# rev1.net
KiCad netlist of a schematic drawn in EAGLE
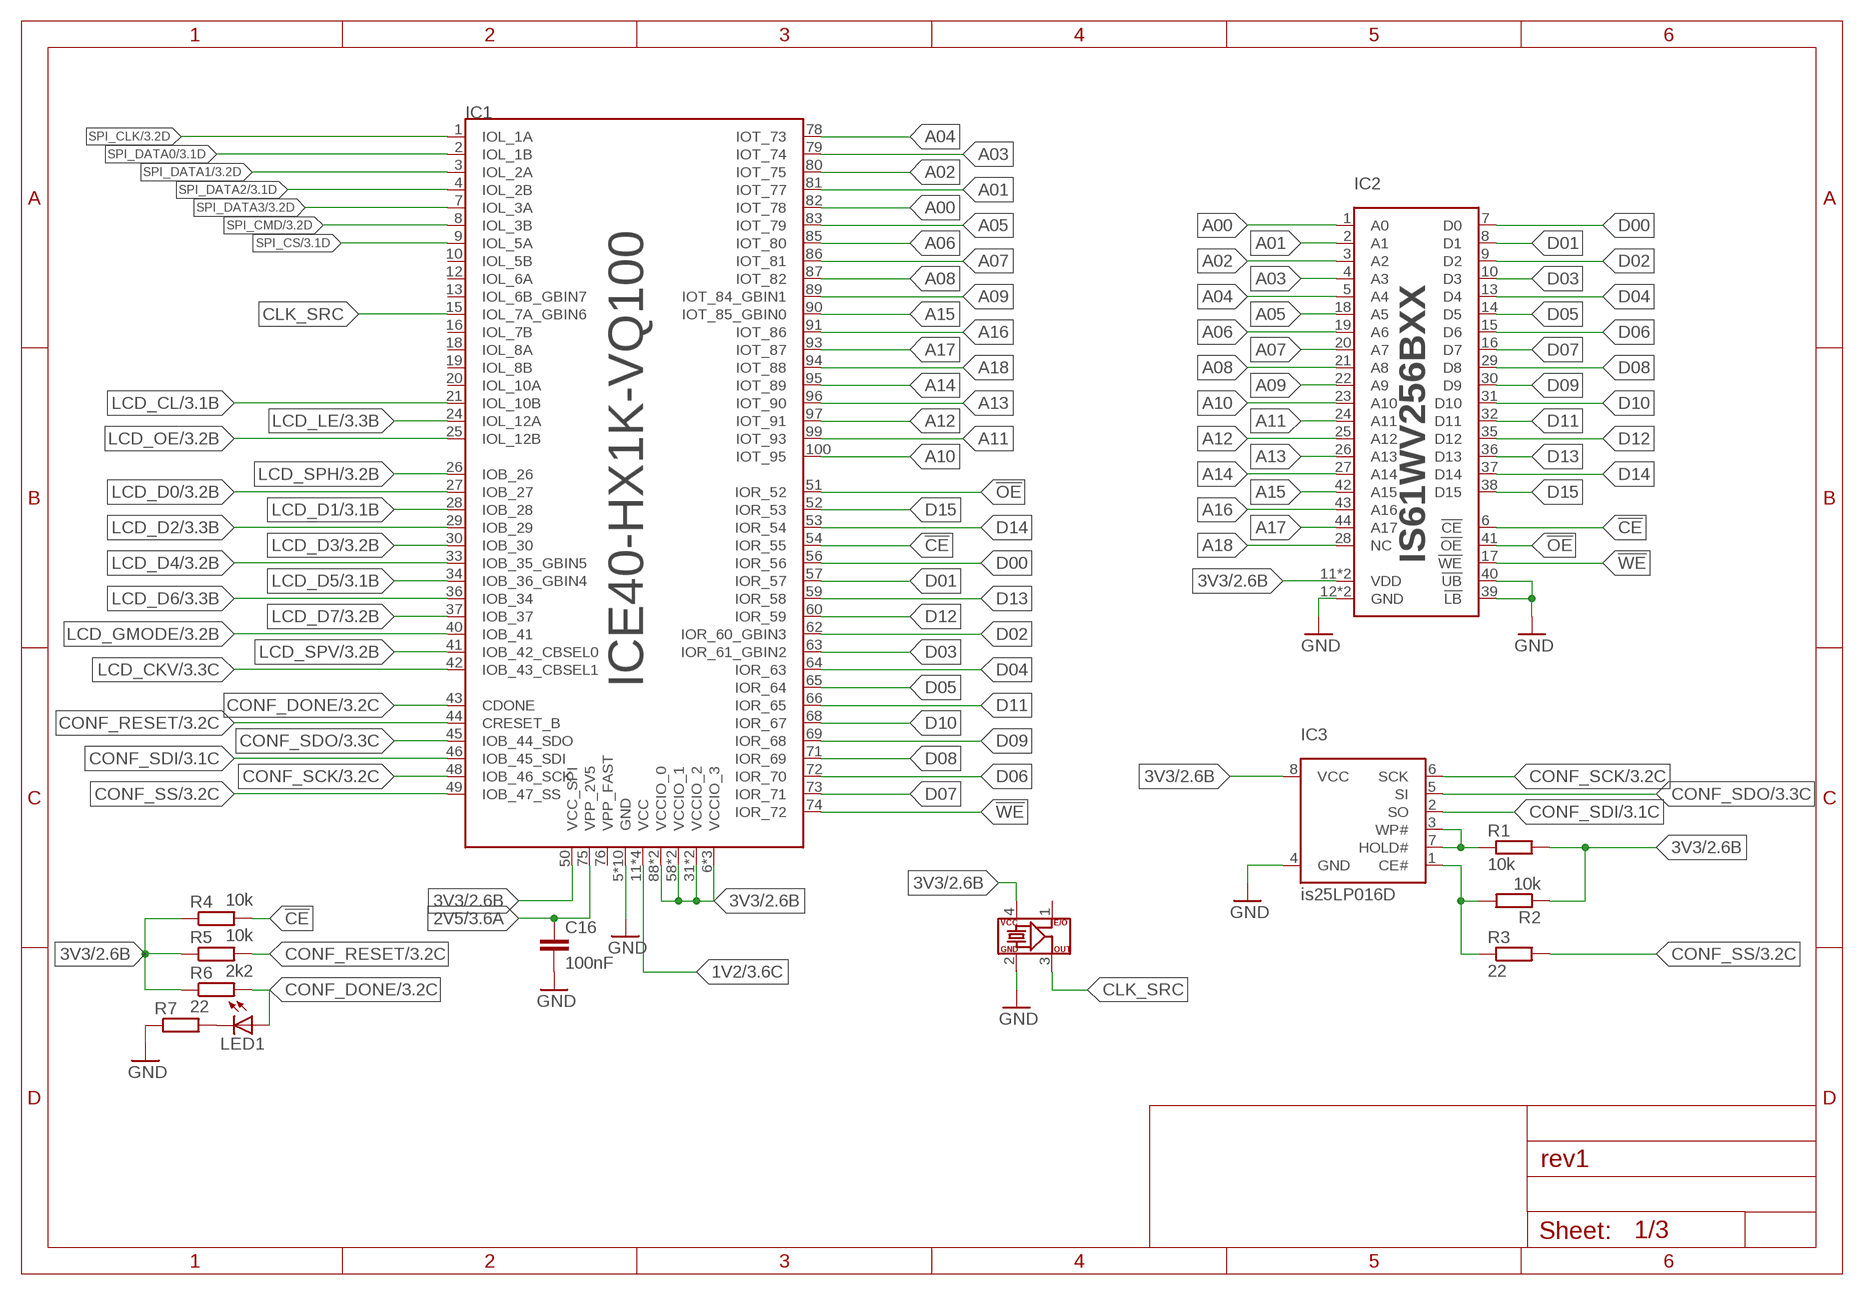
[diagram p0: schematic, sheet 1]
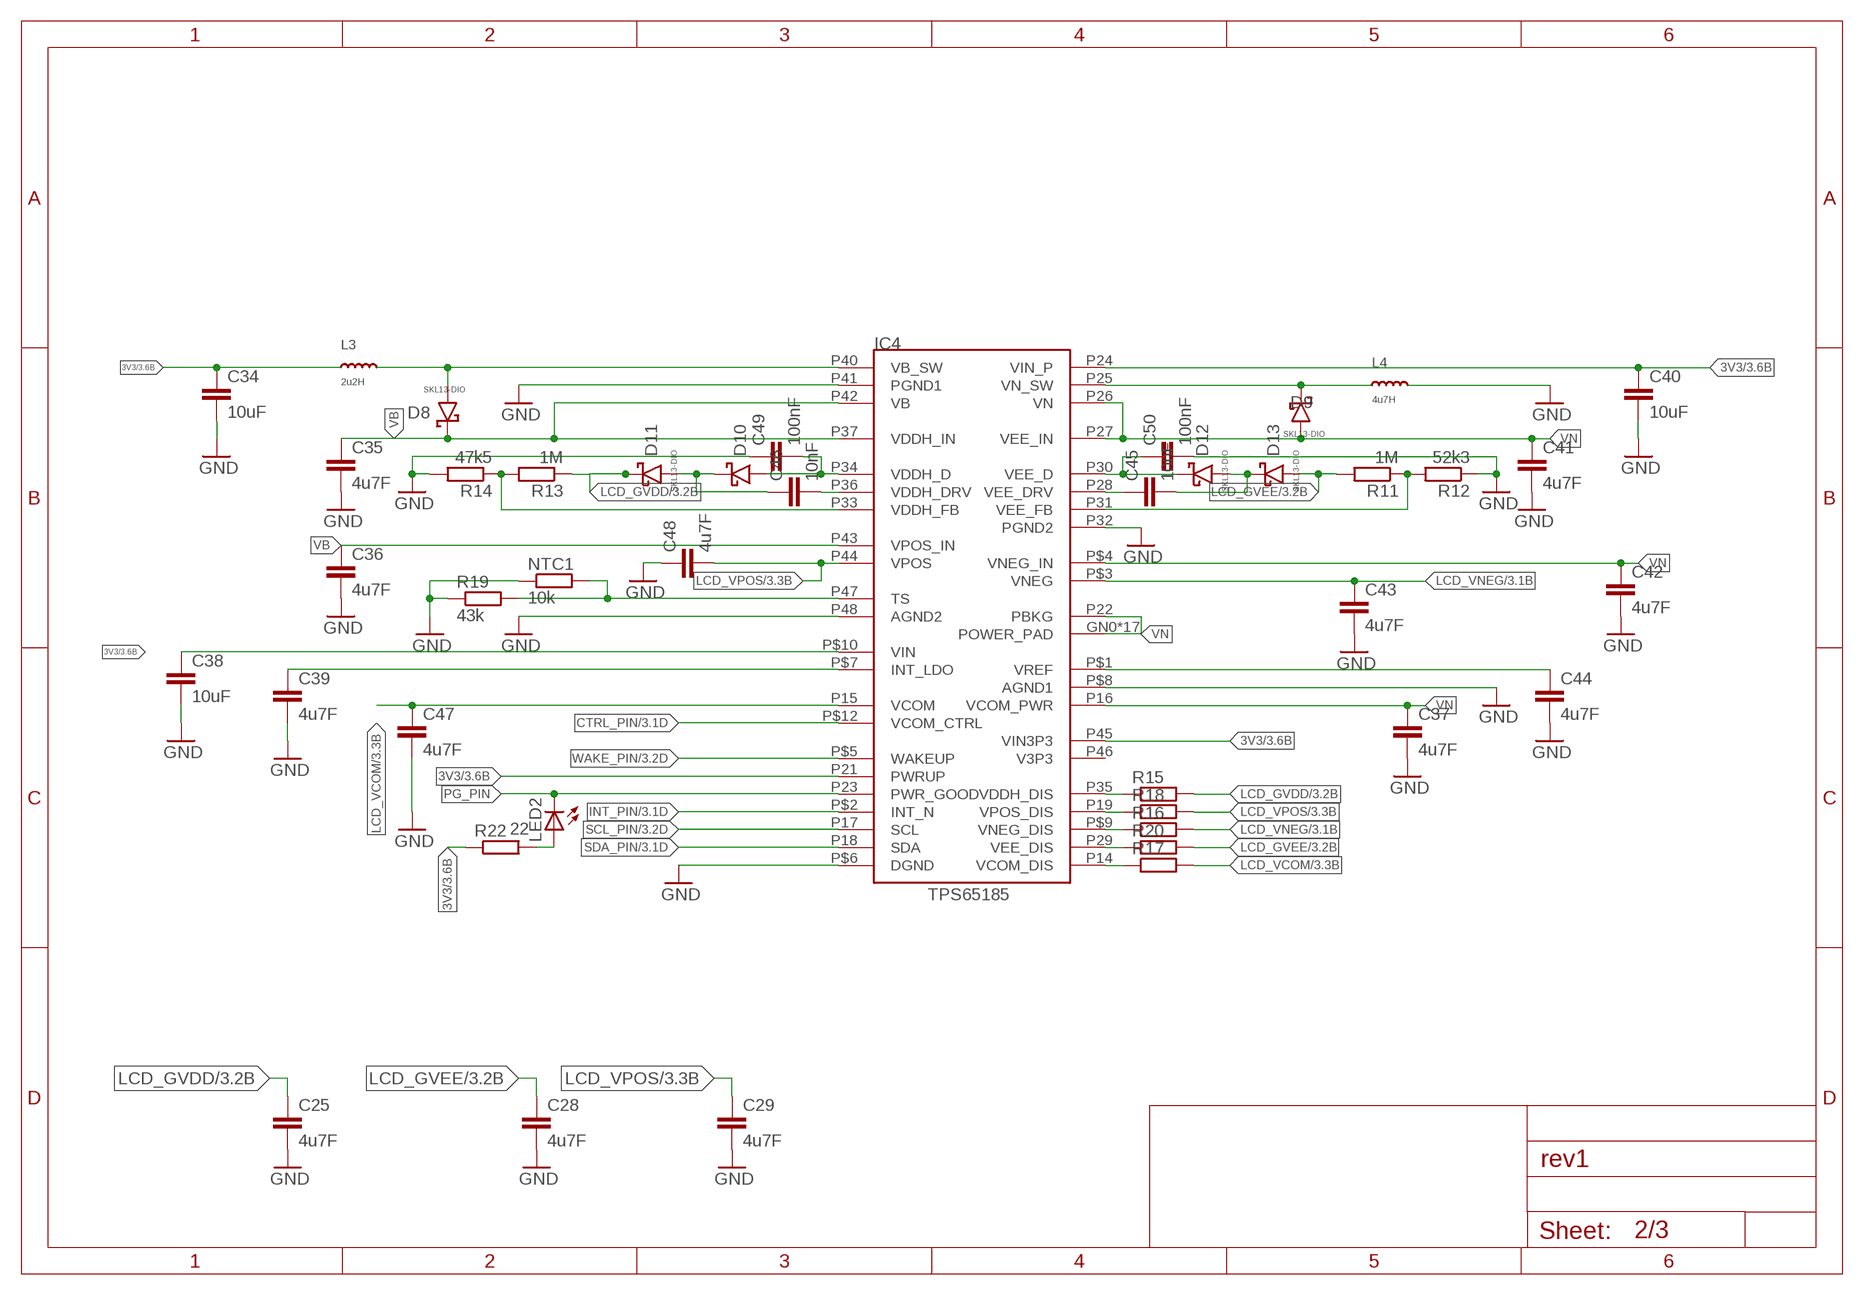
[diagram p1: schematic, sheet 2]
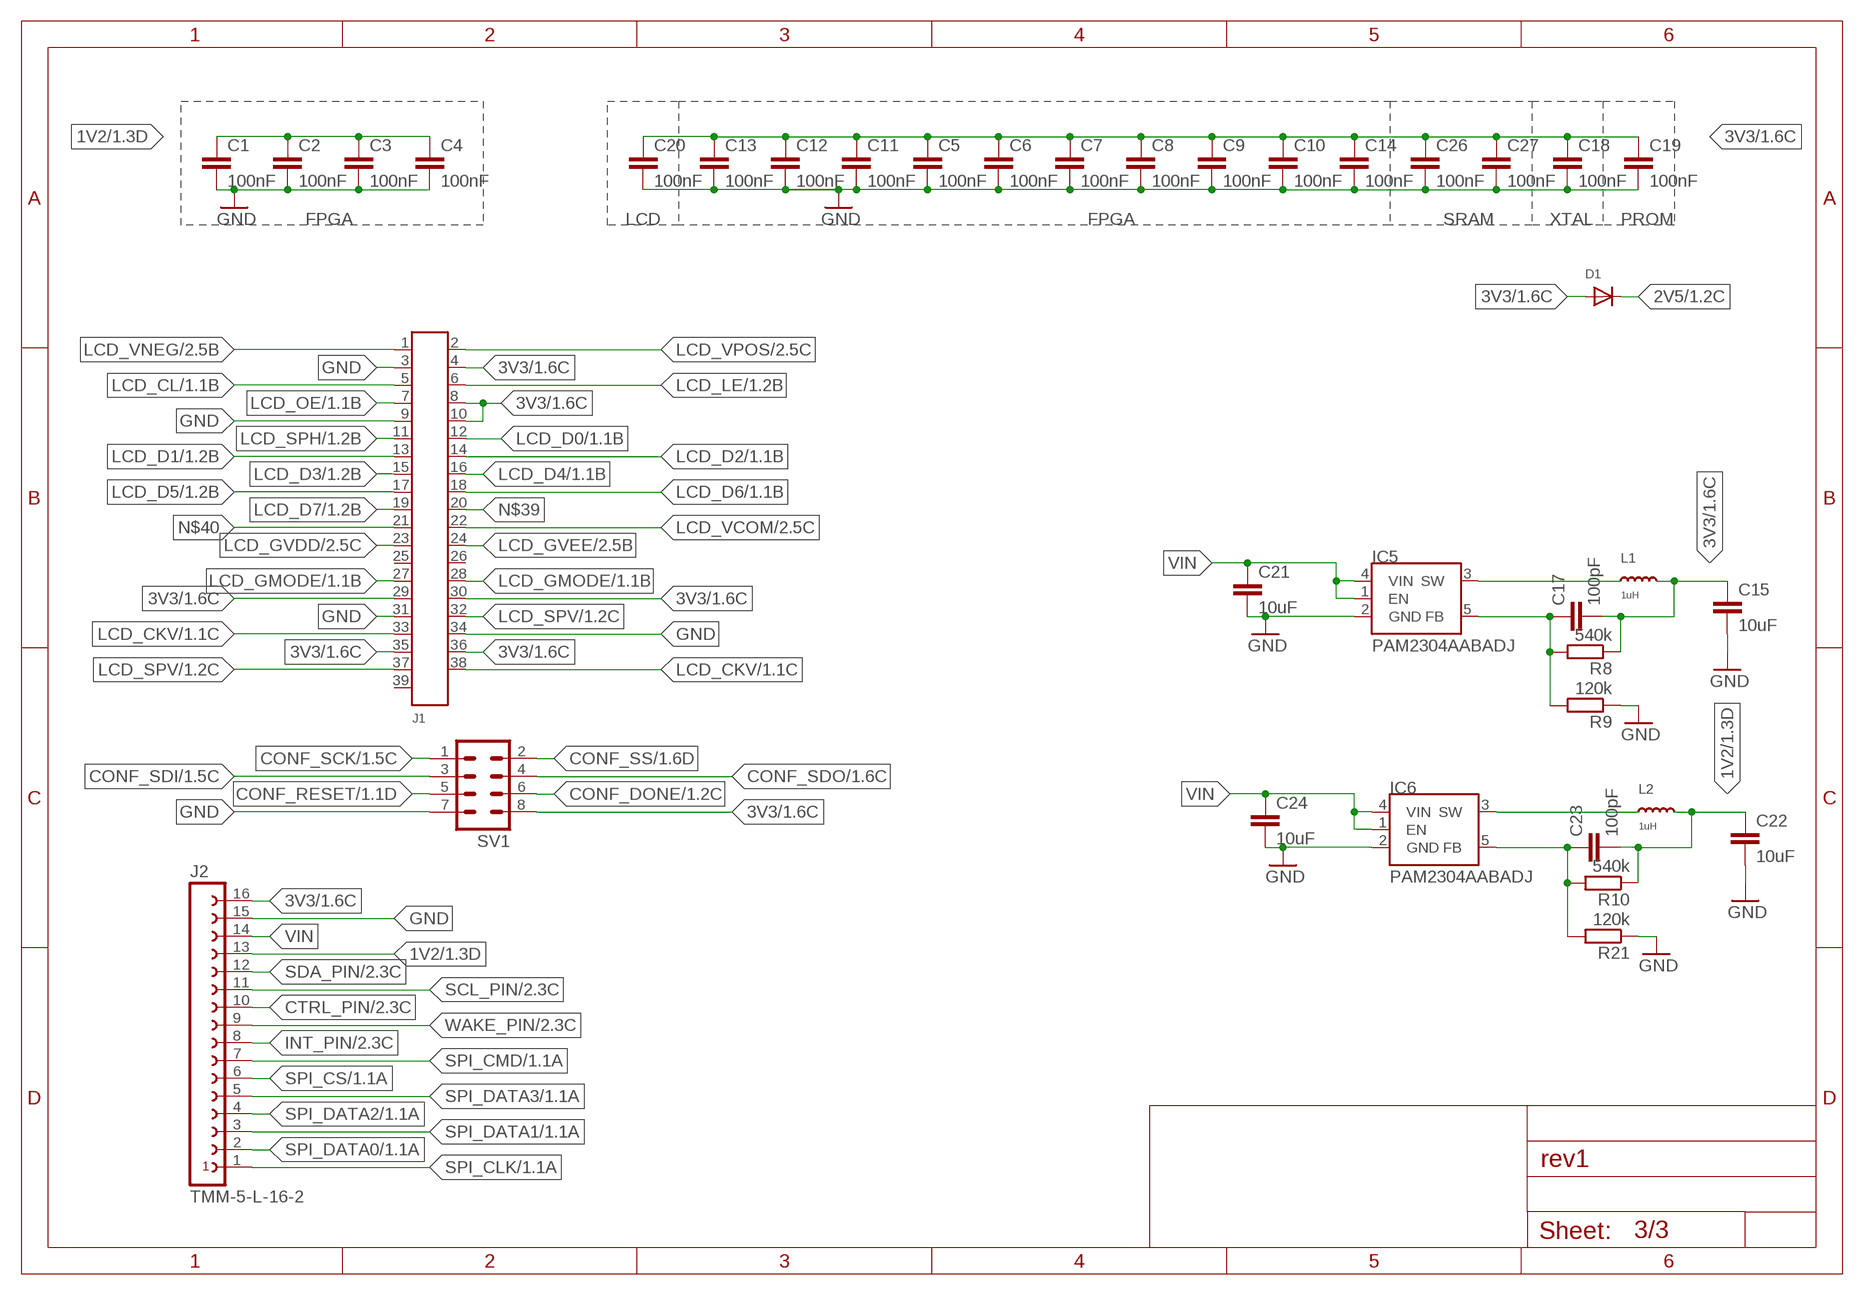
[diagram p2: schematic, sheet 3]

(export (version "E")
  (design (tool "Eeschema 10.0.6"))
  (components
    (comp (ref "C1")
      (value "100nF")
      (footprint "eagle-import:C0402")
      (libsource (lib "eagle-import") (part "C-EUC0402"))
    )
    (comp (ref "C2")
      (value "100nF")
      (footprint "eagle-import:C0402")
      (libsource (lib "eagle-import") (part "C-EUC0402"))
    )
    (comp (ref "C3")
      (value "100nF")
      (footprint "eagle-import:C0402")
      (libsource (lib "eagle-import") (part "C-EUC0402"))
    )
    (comp (ref "C4")
      (value "100nF")
      (footprint "eagle-import:C0402")
      (libsource (lib "eagle-import") (part "C-EUC0402"))
    )
    (comp (ref "C5")
      (value "100nF")
      (footprint "eagle-import:C0402")
      (libsource (lib "eagle-import") (part "C-EUC0402"))
    )
    (comp (ref "C6")
      (value "100nF")
      (footprint "eagle-import:C0402")
      (libsource (lib "eagle-import") (part "C-EUC0402"))
    )
    (comp (ref "C7")
      (value "100nF")
      (footprint "eagle-import:C0402")
      (libsource (lib "eagle-import") (part "C-EUC0402"))
    )
    (comp (ref "C8")
      (value "100nF")
      (footprint "eagle-import:C0402")
      (libsource (lib "eagle-import") (part "C-EUC0402"))
    )
    (comp (ref "C9")
      (value "100nF")
      (footprint "eagle-import:C0402")
      (libsource (lib "eagle-import") (part "C-EUC0402"))
    )
    (comp (ref "C10")
      (value "100nF")
      (footprint "eagle-import:C0402")
      (libsource (lib "eagle-import") (part "C-EUC0402"))
    )
    (comp (ref "C11")
      (value "100nF")
      (footprint "eagle-import:C0402")
      (libsource (lib "eagle-import") (part "C-EUC0402"))
    )
    (comp (ref "C12")
      (value "100nF")
      (footprint "eagle-import:C0402")
      (libsource (lib "eagle-import") (part "C-EUC0402"))
    )
    (comp (ref "C13")
      (value "100nF")
      (footprint "eagle-import:C0402")
      (libsource (lib "eagle-import") (part "C-EUC0402"))
    )
    (comp (ref "C14")
      (value "100nF")
      (footprint "eagle-import:C0402")
      (libsource (lib "eagle-import") (part "C-EUC0402"))
    )
    (comp (ref "C15")
      (value "10uF")
      (footprint "eagle-import:C0603")
      (libsource (lib "eagle-import") (part "C-EUC0603"))
    )
    (comp (ref "C17")
      (value "100pF")
      (footprint "eagle-import:C0402")
      (libsource (lib "eagle-import") (part "C-EUC0402"))
    )
    (comp (ref "C18")
      (value "100nF")
      (footprint "eagle-import:C0402")
      (libsource (lib "eagle-import") (part "C-EUC0402"))
    )
    (comp (ref "C19")
      (value "100nF")
      (footprint "eagle-import:C0402")
      (libsource (lib "eagle-import") (part "C-EUC0402"))
    )
    (comp (ref "C20")
      (value "100nF")
      (footprint "eagle-import:C0402")
      (libsource (lib "eagle-import") (part "C-EUC0402"))
    )
    (comp (ref "C21")
      (value "10uF")
      (footprint "eagle-import:C0603")
      (libsource (lib "eagle-import") (part "C-EUC0603"))
    )
    (comp (ref "C22")
      (value "10uF")
      (footprint "eagle-import:C0603")
      (libsource (lib "eagle-import") (part "C-EUC0603"))
    )
    (comp (ref "C23")
      (value "100pF")
      (footprint "eagle-import:C0402")
      (libsource (lib "eagle-import") (part "C-EUC0402"))
    )
    (comp (ref "C24")
      (value "10uF")
      (footprint "eagle-import:C0603")
      (libsource (lib "eagle-import") (part "C-EUC0603"))
    )
    (comp (ref "C26")
      (value "100nF")
      (footprint "eagle-import:C0402")
      (libsource (lib "eagle-import") (part "C-EUC0402"))
    )
    (comp (ref "C27")
      (value "100nF")
      (footprint "eagle-import:C0402")
      (libsource (lib "eagle-import") (part "C-EUC0402"))
    )
    (comp (ref "D1")
      (value "DIODESOD-123")
      (footprint "eagle-import:SOD-123")
      (libsource (lib "eagle-import") (part "DIODESOD-123"))
    )
    (comp (ref "IC5")
      (value "PAM2304AABADJ")
      (footprint "eagle-import:TSOT25")
      (libsource (lib "eagle-import") (part "PAM2304AABADJ"))
    )
    (comp (ref "IC6")
      (value "PAM2304AABADJ")
      (footprint "eagle-import:TSOT25")
      (libsource (lib "eagle-import") (part "PAM2304AABADJ"))
    )
    (comp (ref "J1")
      (value "FH23-39S-0.3SHW")
      (footprint "eagle-import:FH23-39S-0.3SHW")
      (libsource (lib "eagle-import") (part "FH23-39S-0.3SHW"))
    )
    (comp (ref "J2")
      (value "TMM-5-L-16-2")
      (footprint "eagle-import:TMM-5-L-16-2")
      (libsource (lib "eagle-import") (part "TMM-5-L-16-2"))
    )
    (comp (ref "L1")
      (value "1uH")
      (footprint "eagle-import:3015")
      (libsource (lib "eagle-import") (part "DJNR-3015-1R0"))
    )
    (comp (ref "L2")
      (value "1uH")
      (footprint "eagle-import:3015")
      (libsource (lib "eagle-import") (part "DJNR-3015-1R0"))
    )
    (comp (ref "R8")
      (value "540k")
      (footprint "eagle-import:R0402")
      (libsource (lib "eagle-import") (part "R-EU_R0402"))
    )
    (comp (ref "R9")
      (value "120k")
      (footprint "eagle-import:R0402")
      (libsource (lib "eagle-import") (part "R-EU_R0402"))
    )
    (comp (ref "R10")
      (value "540k")
      (footprint "eagle-import:R0402")
      (libsource (lib "eagle-import") (part "R-EU_R0402"))
    )
    (comp (ref "R21")
      (value "120k")
      (footprint "eagle-import:R0402")
      (libsource (lib "eagle-import") (part "R-EU_R0402"))
    )
    (comp (ref "SV1")
      (value "MA04-2")
      (footprint "eagle-import:MA04-2")
      (libsource (lib "eagle-import") (part "MA04-2"))
    )
    (comp (ref "C25")
      (value "4u7F")
      (footprint "eagle-import:C0805")
      (libsource (lib "eagle-import") (part "C-EUC0805"))
    )
    (comp (ref "C28")
      (value "4u7F")
      (footprint "eagle-import:C0805")
      (libsource (lib "eagle-import") (part "C-EUC0805"))
    )
    (comp (ref "C29")
      (value "4u7F")
      (footprint "eagle-import:C0805")
      (libsource (lib "eagle-import") (part "C-EUC0805"))
    )
    (comp (ref "C34")
      (value "10uF")
      (footprint "eagle-import:C0805")
      (libsource (lib "eagle-import") (part "C-EUC0805"))
    )
    (comp (ref "C35")
      (value "4u7F")
      (footprint "eagle-import:C0805")
      (libsource (lib "eagle-import") (part "C-EUC0805"))
    )
    (comp (ref "C36")
      (value "4u7F")
      (footprint "eagle-import:C0805")
      (libsource (lib "eagle-import") (part "C-EUC0805"))
    )
    (comp (ref "C37")
      (value "4u7F")
      (footprint "eagle-import:C0805")
      (libsource (lib "eagle-import") (part "C-EUC0805"))
    )
    (comp (ref "C38")
      (value "10uF")
      (footprint "eagle-import:C0805")
      (libsource (lib "eagle-import") (part "C-EUC0805"))
    )
    (comp (ref "C39")
      (value "4u7F")
      (footprint "eagle-import:C0603")
      (libsource (lib "eagle-import") (part "C-EUC0603"))
    )
    (comp (ref "C40")
      (value "10uF")
      (footprint "eagle-import:C0805")
      (libsource (lib "eagle-import") (part "C-EUC0805"))
    )
    (comp (ref "C41")
      (value "4u7F")
      (footprint "eagle-import:C0805")
      (libsource (lib "eagle-import") (part "C-EUC0805"))
    )
    (comp (ref "C42")
      (value "4u7F")
      (footprint "eagle-import:C0805")
      (libsource (lib "eagle-import") (part "C-EUC0805"))
    )
    (comp (ref "C43")
      (value "4u7F")
      (footprint "eagle-import:C0805")
      (libsource (lib "eagle-import") (part "C-EUC0805"))
    )
    (comp (ref "C44")
      (value "4u7F")
      (footprint "eagle-import:C0603")
      (libsource (lib "eagle-import") (part "C-EUC0603"))
    )
    (comp (ref "C45")
      (value "10nF")
      (footprint "eagle-import:C0402")
      (libsource (lib "eagle-import") (part "C-EUC0402"))
    )
    (comp (ref "C46")
      (value "10nF")
      (footprint "eagle-import:C0402")
      (libsource (lib "eagle-import") (part "C-EUC0402"))
    )
    (comp (ref "C47")
      (value "4u7F")
      (footprint "eagle-import:C0603")
      (libsource (lib "eagle-import") (part "C-EUC0603"))
    )
    (comp (ref "C48")
      (value "4u7F")
      (footprint "eagle-import:C0805")
      (libsource (lib "eagle-import") (part "C-EUC0805"))
    )
    (comp (ref "C49")
      (value "100nF")
      (footprint "eagle-import:C0402")
      (libsource (lib "eagle-import") (part "C-EUC0402"))
    )
    (comp (ref "C50")
      (value "100nF")
      (footprint "eagle-import:C0402")
      (libsource (lib "eagle-import") (part "C-EUC0402"))
    )
    (comp (ref "D8")
      (value "SKL13-DIO")
      (footprint "eagle-import:SOD523")
      (libsource (lib "eagle-import") (part "RB520S30T"))
    )
    (comp (ref "D9")
      (value "SKL13-DIO")
      (footprint "eagle-import:SOD523")
      (libsource (lib "eagle-import") (part "RB520S30T"))
    )
    (comp (ref "D10")
      (value "SKL13-DIO")
      (footprint "eagle-import:SOD523")
      (libsource (lib "eagle-import") (part "RB520S30T"))
    )
    (comp (ref "D11")
      (value "SKL13-DIO")
      (footprint "eagle-import:SOD523")
      (libsource (lib "eagle-import") (part "RB520S30T"))
    )
    (comp (ref "D12")
      (value "SKL13-DIO")
      (footprint "eagle-import:SOD523")
      (libsource (lib "eagle-import") (part "RB520S30T"))
    )
    (comp (ref "D13")
      (value "SKL13-DIO")
      (footprint "eagle-import:SOD523")
      (libsource (lib "eagle-import") (part "RB520S30T"))
    )
    (comp (ref "IC4")
      (value "TPS65185")
      (footprint "eagle-import:RGZ")
      (libsource (lib "eagle-import") (part "TPS65185"))
    )
    (comp (ref "L3")
      (value "2u2H")
      (footprint "eagle-import:3015")
      (libsource (lib "eagle-import") (part "DJNR-3015-2R2"))
    )
    (comp (ref "L4")
      (value "4u7H")
      (footprint "eagle-import:3015")
      (libsource (lib "eagle-import") (part "DJNR-3015-1R0"))
    )
    (comp (ref "LED2")
      (value "LEDCHIP-LED0603")
      (footprint "eagle-import:CHIP-LED0603")
      (libsource (lib "eagle-import") (part "LEDCHIP-LED0603"))
    )
    (comp (ref "NTC1")
      (value "10k")
      (footprint "eagle-import:R0603")
      (libsource (lib "eagle-import") (part "R-EU_R0603"))
    )
    (comp (ref "R11")
      (value "1M")
      (footprint "eagle-import:R0603")
      (libsource (lib "eagle-import") (part "R-EU_R0603"))
    )
    (comp (ref "R12")
      (value "52k3")
      (footprint "eagle-import:R0603")
      (libsource (lib "eagle-import") (part "R-EU_R0603"))
    )
    (comp (ref "R13")
      (value "1M")
      (footprint "eagle-import:R0603")
      (libsource (lib "eagle-import") (part "R-EU_R0603"))
    )
    (comp (ref "R14")
      (value "47k5")
      (footprint "eagle-import:R0603")
      (libsource (lib "eagle-import") (part "R-EU_R0603"))
    )
    (comp (ref "R15")
      (value "R-EU_R0603")
      (footprint "eagle-import:R0603")
      (libsource (lib "eagle-import") (part "R-EU_R0603"))
    )
    (comp (ref "R16")
      (value "R-EU_R0603")
      (footprint "eagle-import:R0603")
      (libsource (lib "eagle-import") (part "R-EU_R0603"))
    )
    (comp (ref "R17")
      (value "R-EU_R0603")
      (footprint "eagle-import:R0603")
      (libsource (lib "eagle-import") (part "R-EU_R0603"))
    )
    (comp (ref "R18")
      (value "R-EU_R0603")
      (footprint "eagle-import:R0603")
      (libsource (lib "eagle-import") (part "R-EU_R0603"))
    )
    (comp (ref "R19")
      (value "43k")
      (footprint "eagle-import:R0603")
      (libsource (lib "eagle-import") (part "R-EU_R0603"))
    )
    (comp (ref "R20")
      (value "R-EU_R0603")
      (footprint "eagle-import:R0603")
      (libsource (lib "eagle-import") (part "R-EU_R0603"))
    )
    (comp (ref "R22")
      (value "22")
      (footprint "eagle-import:R0402")
      (libsource (lib "eagle-import") (part "R-EU_R0402"))
    )
    (comp (ref "C16")
      (value "100nF")
      (footprint "eagle-import:C0402")
      (libsource (lib "eagle-import") (part "C-EUC0402"))
    )
    (comp (ref "IC1")
      (value "ICE40-HX1K-VQ100")
      (footprint "eagle-import:VQ100")
      (libsource (lib "eagle-import") (part "ICE40-HX1K-VQ100"))
    )
    (comp (ref "IC2")
      (value "IS61WV256BXX")
      (footprint "eagle-import:TSOP-2")
      (libsource (lib "eagle-import") (part "IS61WV256BXX"))
    )
    (comp (ref "IC3")
      (value "is25LP016D")
      (footprint "eagle-import:SOP08")
      (libsource (lib "eagle-import") (part "25LPWP016D"))
    )
    (comp (ref "LED1")
      (value "LEDCHIP-LED0603")
      (footprint "eagle-import:CHIP-LED0603")
      (libsource (lib "eagle-import") (part "LEDCHIP-LED0603"))
    )
    (comp (ref "R1")
      (value "10k")
      (footprint "eagle-import:R0402")
      (libsource (lib "eagle-import") (part "R-EU_R0402"))
    )
    (comp (ref "R2")
      (value "10k")
      (footprint "eagle-import:R0603")
      (libsource (lib "eagle-import") (part "R-EU_R0603"))
    )
    (comp (ref "R3")
      (value "22")
      (footprint "eagle-import:R0402")
      (libsource (lib "eagle-import") (part "R-EU_R0402"))
    )
    (comp (ref "R4")
      (value "10k")
      (footprint "eagle-import:R0402")
      (libsource (lib "eagle-import") (part "R-EU_R0402"))
    )
    (comp (ref "R5")
      (value "10k")
      (footprint "eagle-import:R0402")
      (libsource (lib "eagle-import") (part "R-EU_R0402"))
    )
    (comp (ref "R6")
      (value "2k2")
      (footprint "eagle-import:R0402")
      (libsource (lib "eagle-import") (part "R-EU_R0402"))
    )
    (comp (ref "R7")
      (value "22")
      (footprint "eagle-import:R0402")
      (libsource (lib "eagle-import") (part "R-EU_R0402"))
    )
    (comp (ref "X1")
      (value "DSC61XX")
      (footprint "eagle-import:3225")
      (libsource (lib "eagle-import") (part "DSC61XX"))
    )
  )
  (nets
    (net (code "1") (name "1V2") (class "Default")
      (node (ref "C1") (pin "1") (pinfunction "1_1") (pintype "passive"))
      (node (ref "C2") (pin "1") (pinfunction "1_1") (pintype "passive"))
      (node (ref "C22") (pin "1") (pinfunction "1_1") (pintype "passive"))
      (node (ref "C23") (pin "2") (pinfunction "2_2") (pintype "passive"))
      (node (ref "C3") (pin "1") (pinfunction "1_1") (pintype "passive"))
      (node (ref "C4") (pin "1") (pinfunction "1_1") (pintype "passive"))
      (node (ref "IC1") (pin "11") (pinfunction "VCC_11") (pintype "bidirectional"))
      (node (ref "IC1") (pin "35") (pinfunction "VCC_35") (pintype "bidirectional"))
      (node (ref "IC1") (pin "61") (pinfunction "VCC_61") (pintype "bidirectional"))
      (node (ref "IC1") (pin "77") (pinfunction "VCC_77") (pintype "bidirectional"))
      (node (ref "J2") (pin "13") (pinfunction "13_13") (pintype "passive"))
      (node (ref "L2") (pin "P$2") (pinfunction "P$2_P$2") (pintype "bidirectional"))
      (node (ref "R10") (pin "1") (pinfunction "1_1") (pintype "passive"))
    )
    (net (code "2") (name "2V5") (class "Default")
      (node (ref "C16") (pin "1") (pinfunction "1_1") (pintype "passive"))
      (node (ref "D1") (pin "C") (pinfunction "C_C") (pintype "passive"))
      (node (ref "IC1") (pin "75") (pinfunction "VPP_2V5_75") (pintype "bidirectional"))
    )
    (net (code "3") (name "3V3") (class "Default")
      (node (ref "C10") (pin "1") (pinfunction "1_1") (pintype "passive"))
      (node (ref "C11") (pin "1") (pinfunction "1_1") (pintype "passive"))
      (node (ref "C12") (pin "1") (pinfunction "1_1") (pintype "passive"))
      (node (ref "C13") (pin "1") (pinfunction "1_1") (pintype "passive"))
      (node (ref "C14") (pin "1") (pinfunction "1_1") (pintype "passive"))
      (node (ref "C15") (pin "1") (pinfunction "1_1") (pintype "passive"))
      (node (ref "C17") (pin "2") (pinfunction "2_2") (pintype "passive"))
      (node (ref "C18") (pin "1") (pinfunction "1_1") (pintype "passive"))
      (node (ref "C19") (pin "1") (pinfunction "1_1") (pintype "passive"))
      (node (ref "C20") (pin "1") (pinfunction "1_1") (pintype "passive"))
      (node (ref "C26") (pin "1") (pinfunction "1_1") (pintype "passive"))
      (node (ref "C27") (pin "1") (pinfunction "1_1") (pintype "passive"))
      (node (ref "C34") (pin "1") (pinfunction "1_1") (pintype "passive"))
      (node (ref "C38") (pin "1") (pinfunction "1_1") (pintype "passive"))
      (node (ref "C40") (pin "1") (pinfunction "1_1") (pintype "passive"))
      (node (ref "C5") (pin "1") (pinfunction "1_1") (pintype "passive"))
      (node (ref "C6") (pin "1") (pinfunction "1_1") (pintype "passive"))
      (node (ref "C7") (pin "1") (pinfunction "1_1") (pintype "passive"))
      (node (ref "C8") (pin "1") (pinfunction "1_1") (pintype "passive"))
      (node (ref "C9") (pin "1") (pinfunction "1_1") (pintype "passive"))
      (node (ref "D1") (pin "A") (pinfunction "A_A") (pintype "passive"))
      (node (ref "IC1") (pin "14") (pinfunction "VCCIO_3_14") (pintype "bidirectional"))
      (node (ref "IC1") (pin "22") (pinfunction "VCCIO_3_22") (pintype "bidirectional"))
      (node (ref "IC1") (pin "31") (pinfunction "VCCIO_2_31") (pintype "bidirectional"))
      (node (ref "IC1") (pin "38") (pinfunction "VCCIO_2_38") (pintype "bidirectional"))
      (node (ref "IC1") (pin "50") (pinfunction "VCC_SPI_50") (pintype "bidirectional"))
      (node (ref "IC1") (pin "58") (pinfunction "VCCIO_1_58") (pintype "bidirectional"))
      (node (ref "IC1") (pin "6") (pinfunction "VCCIO_3_6") (pintype "bidirectional"))
      (node (ref "IC1") (pin "67") (pinfunction "VCCIO_1_67") (pintype "bidirectional"))
      (node (ref "IC1") (pin "88") (pinfunction "VCCIO_0_88") (pintype "bidirectional"))
      (node (ref "IC1") (pin "92") (pinfunction "VCCIO_0_92") (pintype "bidirectional"))
      (node (ref "IC2") (pin "11") (pinfunction "VDD_11") (pintype "bidirectional"))
      (node (ref "IC2") (pin "33") (pinfunction "VDD_33") (pintype "bidirectional"))
      (node (ref "IC3") (pin "8") (pinfunction "VCC_8") (pintype "bidirectional"))
      (node (ref "IC4") (pin "P$10") (pinfunction "VIN_P$10") (pintype "bidirectional"))
      (node (ref "IC4") (pin "P21") (pinfunction "PWRUP_P21") (pintype "bidirectional"))
      (node (ref "IC4") (pin "P24") (pinfunction "VIN_P_P24") (pintype "bidirectional"))
      (node (ref "IC4") (pin "P45") (pinfunction "VIN3P3_P45") (pintype "bidirectional"))
      (node (ref "J1") (pin "10") (pinfunction "10_10") (pintype "bidirectional"))
      (node (ref "J1") (pin "29") (pinfunction "29_29") (pintype "bidirectional"))
      (node (ref "J1") (pin "30") (pinfunction "30_30") (pintype "bidirectional"))
      (node (ref "J1") (pin "35") (pinfunction "35_35") (pintype "bidirectional"))
      (node (ref "J1") (pin "36") (pinfunction "36_36") (pintype "bidirectional"))
      (node (ref "J1") (pin "4") (pinfunction "4_4") (pintype "bidirectional"))
      (node (ref "J1") (pin "8") (pinfunction "8_8") (pintype "bidirectional"))
      (node (ref "J2") (pin "16") (pinfunction "16_16") (pintype "passive"))
      (node (ref "L1") (pin "P$2") (pinfunction "P$2_P$2") (pintype "bidirectional"))
      (node (ref "L3") (pin "P$1") (pinfunction "P$1_P$1") (pintype "bidirectional"))
      (node (ref "R1") (pin "2") (pinfunction "2_2") (pintype "passive"))
      (node (ref "R2") (pin "1") (pinfunction "1_1") (pintype "passive"))
      (node (ref "R22") (pin "1") (pinfunction "1_1") (pintype "passive"))
      (node (ref "R4") (pin "1") (pinfunction "1_1") (pintype "passive"))
      (node (ref "R5") (pin "1") (pinfunction "1_1") (pintype "passive"))
      (node (ref "R6") (pin "1") (pinfunction "1_1") (pintype "passive"))
      (node (ref "R8") (pin "1") (pinfunction "1_1") (pintype "passive"))
      (node (ref "SV1") (pin "8") (pinfunction "8_8") (pintype "passive"))
      (node (ref "X1") (pin "4") (pinfunction "4_4") (pintype "bidirectional"))
    )
    (net (code "4") (name "A00") (class "Default")
      (node (ref "IC1") (pin "82") (pinfunction "IOT_78_82") (pintype "bidirectional"))
      (node (ref "IC2") (pin "1") (pinfunction "A0_1") (pintype "bidirectional"))
    )
    (net (code "5") (name "A01") (class "Default")
      (node (ref "IC1") (pin "81") (pinfunction "IOT_77_81") (pintype "bidirectional"))
      (node (ref "IC2") (pin "2") (pinfunction "A1_2") (pintype "bidirectional"))
    )
    (net (code "6") (name "A02") (class "Default")
      (node (ref "IC1") (pin "80") (pinfunction "IOT_75_80") (pintype "bidirectional"))
      (node (ref "IC2") (pin "3") (pinfunction "A2_3") (pintype "bidirectional"))
    )
    (net (code "7") (name "A03") (class "Default")
      (node (ref "IC1") (pin "79") (pinfunction "IOT_74_79") (pintype "bidirectional"))
      (node (ref "IC2") (pin "4") (pinfunction "A3_4") (pintype "bidirectional"))
    )
    (net (code "8") (name "A04") (class "Default")
      (node (ref "IC1") (pin "78") (pinfunction "IOT_73_78") (pintype "bidirectional"))
      (node (ref "IC2") (pin "5") (pinfunction "A4_5") (pintype "bidirectional"))
    )
    (net (code "9") (name "A05") (class "Default")
      (node (ref "IC1") (pin "83") (pinfunction "IOT_79_83") (pintype "bidirectional"))
      (node (ref "IC2") (pin "18") (pinfunction "A5_18") (pintype "bidirectional"))
    )
    (net (code "10") (name "A06") (class "Default")
      (node (ref "IC1") (pin "85") (pinfunction "IOT_80_85") (pintype "bidirectional"))
      (node (ref "IC2") (pin "19") (pinfunction "A6_19") (pintype "bidirectional"))
    )
    (net (code "11") (name "A07") (class "Default")
      (node (ref "IC1") (pin "86") (pinfunction "IOT_81_86") (pintype "bidirectional"))
      (node (ref "IC2") (pin "20") (pinfunction "A7_20") (pintype "bidirectional"))
    )
    (net (code "12") (name "A08") (class "Default")
      (node (ref "IC1") (pin "87") (pinfunction "IOT_82_87") (pintype "bidirectional"))
      (node (ref "IC2") (pin "21") (pinfunction "A8_21") (pintype "bidirectional"))
    )
    (net (code "13") (name "A09") (class "Default")
      (node (ref "IC1") (pin "89") (pinfunction "IOT_84_GBIN1_89") (pintype "bidirectional"))
      (node (ref "IC2") (pin "22") (pinfunction "A9_22") (pintype "bidirectional"))
    )
    (net (code "14") (name "A10") (class "Default")
      (node (ref "IC1") (pin "100") (pinfunction "IOT_95_100") (pintype "bidirectional"))
      (node (ref "IC2") (pin "23") (pinfunction "A10_23") (pintype "bidirectional"))
    )
    (net (code "15") (name "A11") (class "Default")
      (node (ref "IC1") (pin "99") (pinfunction "IOT_93_99") (pintype "bidirectional"))
      (node (ref "IC2") (pin "24") (pinfunction "A11_24") (pintype "bidirectional"))
    )
    (net (code "16") (name "A12") (class "Default")
      (node (ref "IC1") (pin "97") (pinfunction "IOT_91_97") (pintype "bidirectional"))
      (node (ref "IC2") (pin "25") (pinfunction "A12_25") (pintype "bidirectional"))
    )
    (net (code "17") (name "A13") (class "Default")
      (node (ref "IC1") (pin "96") (pinfunction "IOT_90_96") (pintype "bidirectional"))
      (node (ref "IC2") (pin "26") (pinfunction "A13_26") (pintype "bidirectional"))
    )
    (net (code "18") (name "A14") (class "Default")
      (node (ref "IC1") (pin "95") (pinfunction "IOT_89_95") (pintype "bidirectional"))
      (node (ref "IC2") (pin "27") (pinfunction "A14_27") (pintype "bidirectional"))
    )
    (net (code "19") (name "A15") (class "Default")
      (node (ref "IC1") (pin "90") (pinfunction "IOT_85_GBIN0_90") (pintype "bidirectional"))
      (node (ref "IC2") (pin "42") (pinfunction "A15_42") (pintype "bidirectional"))
    )
    (net (code "20") (name "A16") (class "Default")
      (node (ref "IC1") (pin "91") (pinfunction "IOT_86_91") (pintype "bidirectional"))
      (node (ref "IC2") (pin "43") (pinfunction "A16_43") (pintype "bidirectional"))
    )
    (net (code "21") (name "A17") (class "Default")
      (node (ref "IC1") (pin "93") (pinfunction "IOT_87_93") (pintype "bidirectional"))
      (node (ref "IC2") (pin "44") (pinfunction "A17_44") (pintype "bidirectional"))
    )
    (net (code "22") (name "A18") (class "Default")
      (node (ref "IC1") (pin "94") (pinfunction "IOT_88_94") (pintype "bidirectional"))
      (node (ref "IC2") (pin "28") (pinfunction "NC_28") (pintype "bidirectional"))
    )
    (net (code "23") (name "CLK_SRC") (class "Default")
      (node (ref "IC1") (pin "15") (pinfunction "IOL_7A_GBIN6_15") (pintype "bidirectional"))
      (node (ref "X1") (pin "3") (pinfunction "3_3") (pintype "bidirectional"))
    )
    (net (code "24") (name "CONF_DONE") (class "Default")
      (node (ref "IC1") (pin "43") (pinfunction "CDONE_43") (pintype "bidirectional"))
      (node (ref "LED1") (pin "A") (pinfunction "A_A") (pintype "passive"))
      (node (ref "R6") (pin "2") (pinfunction "2_2") (pintype "passive"))
      (node (ref "SV1") (pin "6") (pinfunction "6_6") (pintype "passive"))
    )
    (net (code "25") (name "CONF_RESET") (class "Default")
      (node (ref "IC1") (pin "44") (pinfunction "CRESET_B_44") (pintype "bidirectional"))
      (node (ref "R5") (pin "2") (pinfunction "2_2") (pintype "passive"))
      (node (ref "SV1") (pin "5") (pinfunction "5_5") (pintype "passive"))
    )
    (net (code "26") (name "CONF_SCK") (class "Default")
      (node (ref "IC1") (pin "48") (pinfunction "IOB_46_SCK_48") (pintype "bidirectional"))
      (node (ref "IC3") (pin "6") (pinfunction "SCK_6") (pintype "bidirectional"))
      (node (ref "SV1") (pin "1") (pinfunction "1_1") (pintype "passive"))
    )
    (net (code "27") (name "CONF_SDI") (class "Default")
      (node (ref "IC1") (pin "46") (pinfunction "IOB_45_SDI_46") (pintype "bidirectional"))
      (node (ref "IC3") (pin "2") (pinfunction "SO_2") (pintype "bidirectional"))
      (node (ref "SV1") (pin "3") (pinfunction "3_3") (pintype "passive"))
    )
    (net (code "28") (name "CONF_SDO") (class "Default")
      (node (ref "IC1") (pin "45") (pinfunction "IOB_44_SDO_45") (pintype "bidirectional"))
      (node (ref "IC3") (pin "5") (pinfunction "SI_5") (pintype "bidirectional"))
      (node (ref "SV1") (pin "4") (pinfunction "4_4") (pintype "passive"))
    )
    (net (code "29") (name "CONF_SS") (class "Default")
      (node (ref "IC1") (pin "49") (pinfunction "IOB_47_SS_49") (pintype "bidirectional"))
      (node (ref "R3") (pin "2") (pinfunction "2_2") (pintype "passive"))
      (node (ref "SV1") (pin "2") (pinfunction "2_2") (pintype "passive"))
    )
    (net (code "30") (name "CTRL_PIN") (class "Default")
      (node (ref "IC4") (pin "P$12") (pinfunction "VCOM_CTRL_P$12") (pintype "bidirectional"))
      (node (ref "J2") (pin "10") (pinfunction "10_10") (pintype "passive"))
    )
    (net (code "31") (name "D00") (class "Default")
      (node (ref "IC1") (pin "56") (pinfunction "IOR_56_56") (pintype "bidirectional"))
      (node (ref "IC2") (pin "7") (pinfunction "D0_7") (pintype "bidirectional"))
    )
    (net (code "32") (name "D01") (class "Default")
      (node (ref "IC1") (pin "57") (pinfunction "IOR_57_57") (pintype "bidirectional"))
      (node (ref "IC2") (pin "8") (pinfunction "D1_8") (pintype "bidirectional"))
    )
    (net (code "33") (name "D02") (class "Default")
      (node (ref "IC1") (pin "62") (pinfunction "IOR_60_GBIN3_62") (pintype "bidirectional"))
      (node (ref "IC2") (pin "9") (pinfunction "D2_9") (pintype "bidirectional"))
    )
    (net (code "34") (name "D03") (class "Default")
      (node (ref "IC1") (pin "63") (pinfunction "IOR_61_GBIN2_63") (pintype "bidirectional"))
      (node (ref "IC2") (pin "10") (pinfunction "D3_10") (pintype "bidirectional"))
    )
    (net (code "35") (name "D04") (class "Default")
      (node (ref "IC1") (pin "64") (pinfunction "IOR_63_64") (pintype "bidirectional"))
      (node (ref "IC2") (pin "13") (pinfunction "D4_13") (pintype "bidirectional"))
    )
    (net (code "36") (name "D05") (class "Default")
      (node (ref "IC1") (pin "65") (pinfunction "IOR_64_65") (pintype "bidirectional"))
      (node (ref "IC2") (pin "14") (pinfunction "D5_14") (pintype "bidirectional"))
    )
    (net (code "37") (name "D06") (class "Default")
      (node (ref "IC1") (pin "72") (pinfunction "IOR_70_72") (pintype "bidirectional"))
      (node (ref "IC2") (pin "15") (pinfunction "D6_15") (pintype "bidirectional"))
    )
    (net (code "38") (name "D07") (class "Default")
      (node (ref "IC1") (pin "73") (pinfunction "IOR_71_73") (pintype "bidirectional"))
      (node (ref "IC2") (pin "16") (pinfunction "D7_16") (pintype "bidirectional"))
    )
    (net (code "39") (name "D08") (class "Default")
      (node (ref "IC1") (pin "71") (pinfunction "IOR_69_71") (pintype "bidirectional"))
      (node (ref "IC2") (pin "29") (pinfunction "D8_29") (pintype "bidirectional"))
    )
    (net (code "40") (name "D09") (class "Default")
      (node (ref "IC1") (pin "69") (pinfunction "IOR_68_69") (pintype "bidirectional"))
      (node (ref "IC2") (pin "30") (pinfunction "D9_30") (pintype "bidirectional"))
    )
    (net (code "41") (name "D10") (class "Default")
      (node (ref "IC1") (pin "68") (pinfunction "IOR_67_68") (pintype "bidirectional"))
      (node (ref "IC2") (pin "31") (pinfunction "D10_31") (pintype "bidirectional"))
    )
    (net (code "42") (name "D11") (class "Default")
      (node (ref "IC1") (pin "66") (pinfunction "IOR_65_66") (pintype "bidirectional"))
      (node (ref "IC2") (pin "32") (pinfunction "D11_32") (pintype "bidirectional"))
    )
    (net (code "43") (name "D12") (class "Default")
      (node (ref "IC1") (pin "60") (pinfunction "IOR_59_60") (pintype "bidirectional"))
      (node (ref "IC2") (pin "35") (pinfunction "D12_35") (pintype "bidirectional"))
    )
    (net (code "44") (name "D13") (class "Default")
      (node (ref "IC1") (pin "59") (pinfunction "IOR_58_59") (pintype "bidirectional"))
      (node (ref "IC2") (pin "36") (pinfunction "D13_36") (pintype "bidirectional"))
    )
    (net (code "45") (name "D14") (class "Default")
      (node (ref "IC1") (pin "53") (pinfunction "IOR_54_53") (pintype "bidirectional"))
      (node (ref "IC2") (pin "37") (pinfunction "D14_37") (pintype "bidirectional"))
    )
    (net (code "46") (name "D15") (class "Default")
      (node (ref "IC1") (pin "52") (pinfunction "IOR_53_52") (pintype "bidirectional"))
      (node (ref "IC2") (pin "38") (pinfunction "D15_38") (pintype "bidirectional"))
    )
    (net (code "47") (name "GND") (class "Default")
      (node (ref "C1") (pin "2") (pinfunction "2_2") (pintype "passive"))
      (node (ref "C10") (pin "2") (pinfunction "2_2") (pintype "passive"))
      (node (ref "C11") (pin "2") (pinfunction "2_2") (pintype "passive"))
      (node (ref "C12") (pin "2") (pinfunction "2_2") (pintype "passive"))
      (node (ref "C13") (pin "2") (pinfunction "2_2") (pintype "passive"))
      (node (ref "C14") (pin "2") (pinfunction "2_2") (pintype "passive"))
      (node (ref "C15") (pin "2") (pinfunction "2_2") (pintype "passive"))
      (node (ref "C16") (pin "2") (pinfunction "2_2") (pintype "passive"))
      (node (ref "C18") (pin "2") (pinfunction "2_2") (pintype "passive"))
      (node (ref "C19") (pin "2") (pinfunction "2_2") (pintype "passive"))
      (node (ref "C2") (pin "2") (pinfunction "2_2") (pintype "passive"))
      (node (ref "C20") (pin "2") (pinfunction "2_2") (pintype "passive"))
      (node (ref "C21") (pin "2") (pinfunction "2_2") (pintype "passive"))
      (node (ref "C22") (pin "2") (pinfunction "2_2") (pintype "passive"))
      (node (ref "C24") (pin "2") (pinfunction "2_2") (pintype "passive"))
      (node (ref "C25") (pin "2") (pinfunction "2_2") (pintype "passive"))
      (node (ref "C26") (pin "2") (pinfunction "2_2") (pintype "passive"))
      (node (ref "C27") (pin "2") (pinfunction "2_2") (pintype "passive"))
      (node (ref "C28") (pin "2") (pinfunction "2_2") (pintype "passive"))
      (node (ref "C29") (pin "2") (pinfunction "2_2") (pintype "passive"))
      (node (ref "C3") (pin "2") (pinfunction "2_2") (pintype "passive"))
      (node (ref "C34") (pin "2") (pinfunction "2_2") (pintype "passive"))
      (node (ref "C35") (pin "2") (pinfunction "2_2") (pintype "passive"))
      (node (ref "C36") (pin "2") (pinfunction "2_2") (pintype "passive"))
      (node (ref "C37") (pin "2") (pinfunction "2_2") (pintype "passive"))
      (node (ref "C38") (pin "2") (pinfunction "2_2") (pintype "passive"))
      (node (ref "C39") (pin "2") (pinfunction "2_2") (pintype "passive"))
      (node (ref "C4") (pin "2") (pinfunction "2_2") (pintype "passive"))
      (node (ref "C40") (pin "2") (pinfunction "2_2") (pintype "passive"))
      (node (ref "C41") (pin "2") (pinfunction "2_2") (pintype "passive"))
      (node (ref "C42") (pin "2") (pinfunction "2_2") (pintype "passive"))
      (node (ref "C43") (pin "2") (pinfunction "2_2") (pintype "passive"))
      (node (ref "C44") (pin "2") (pinfunction "2_2") (pintype "passive"))
      (node (ref "C47") (pin "2") (pinfunction "2_2") (pintype "passive"))
      (node (ref "C48") (pin "1") (pinfunction "1_1") (pintype "passive"))
      (node (ref "C49") (pin "1") (pinfunction "1_1") (pintype "passive"))
      (node (ref "C5") (pin "2") (pinfunction "2_2") (pintype "passive"))
      (node (ref "C50") (pin "2") (pinfunction "2_2") (pintype "passive"))
      (node (ref "C6") (pin "2") (pinfunction "2_2") (pintype "passive"))
      (node (ref "C7") (pin "2") (pinfunction "2_2") (pintype "passive"))
      (node (ref "C8") (pin "2") (pinfunction "2_2") (pintype "passive"))
      (node (ref "C9") (pin "2") (pinfunction "2_2") (pintype "passive"))
      (node (ref "IC1") (pin "17") (pinfunction "GND_17") (pintype "bidirectional"))
      (node (ref "IC1") (pin "23") (pinfunction "GND_23") (pintype "bidirectional"))
      (node (ref "IC1") (pin "32") (pinfunction "GND_32") (pintype "bidirectional"))
      (node (ref "IC1") (pin "39") (pinfunction "GND_39") (pintype "bidirectional"))
      (node (ref "IC1") (pin "47") (pinfunction "GND_47") (pintype "bidirectional"))
      (node (ref "IC1") (pin "5") (pinfunction "GND_5") (pintype "bidirectional"))
      (node (ref "IC1") (pin "55") (pinfunction "GND_55") (pintype "bidirectional"))
      (node (ref "IC1") (pin "70") (pinfunction "GND_70") (pintype "bidirectional"))
      (node (ref "IC1") (pin "84") (pinfunction "GND_84") (pintype "bidirectional"))
      (node (ref "IC1") (pin "98") (pinfunction "GND_98") (pintype "bidirectional"))
      (node (ref "IC2") (pin "12") (pinfunction "GND_12") (pintype "bidirectional"))
      (node (ref "IC2") (pin "34") (pinfunction "GND_34") (pintype "bidirectional"))
      (node (ref "IC2") (pin "39") (pinfunction "~{LB}_39") (pintype "bidirectional"))
      (node (ref "IC2") (pin "40") (pinfunction "~{UB}_40") (pintype "bidirectional"))
      (node (ref "IC3") (pin "4") (pinfunction "GND_4") (pintype "bidirectional"))
      (node (ref "IC4") (pin "P$6") (pinfunction "DGND_P$6") (pintype "bidirectional"))
      (node (ref "IC4") (pin "P$8") (pinfunction "AGND1_P$8") (pintype "bidirectional"))
      (node (ref "IC4") (pin "P32") (pinfunction "PGND2_P32") (pintype "bidirectional"))
      (node (ref "IC4") (pin "P41") (pinfunction "PGND1_P41") (pintype "bidirectional"))
      (node (ref "IC4") (pin "P48") (pinfunction "AGND2_P48") (pintype "bidirectional"))
      (node (ref "IC5") (pin "2") (pinfunction "GND_2") (pintype "bidirectional"))
      (node (ref "IC6") (pin "2") (pinfunction "GND_2") (pintype "bidirectional"))
      (node (ref "J1") (pin "3") (pinfunction "3_3") (pintype "bidirectional"))
      (node (ref "J1") (pin "31") (pinfunction "31_31") (pintype "bidirectional"))
      (node (ref "J1") (pin "34") (pinfunction "34_34") (pintype "bidirectional"))
      (node (ref "J1") (pin "9") (pinfunction "9_9") (pintype "bidirectional"))
      (node (ref "J2") (pin "15") (pinfunction "15_15") (pintype "passive"))
      (node (ref "L4") (pin "P$2") (pinfunction "P$2_P$2") (pintype "bidirectional"))
      (node (ref "NTC1") (pin "1") (pinfunction "1_1") (pintype "passive"))
      (node (ref "R12") (pin "1") (pinfunction "1_1") (pintype "passive"))
      (node (ref "R14") (pin "2") (pinfunction "2_2") (pintype "passive"))
      (node (ref "R19") (pin "1") (pinfunction "1_1") (pintype "passive"))
      (node (ref "R21") (pin "1") (pinfunction "1_1") (pintype "passive"))
      (node (ref "R7") (pin "1") (pinfunction "1_1") (pintype "passive"))
      (node (ref "R9") (pin "1") (pinfunction "1_1") (pintype "passive"))
      (node (ref "SV1") (pin "7") (pinfunction "7_7") (pintype "passive"))
      (node (ref "X1") (pin "2") (pinfunction "2_2") (pintype "bidirectional"))
    )
    (net (code "48") (name "INT_PIN") (class "Default")
      (node (ref "IC4") (pin "P$2") (pinfunction "INT_N_P$2") (pintype "bidirectional"))
      (node (ref "J2") (pin "8") (pinfunction "8_8") (pintype "passive"))
    )
    (net (code "49") (name "LCD_CKV") (class "Default")
      (node (ref "IC1") (pin "42") (pinfunction "IOB_43_CBSEL1_42") (pintype "bidirectional"))
      (node (ref "J1") (pin "33") (pinfunction "33_33") (pintype "bidirectional"))
      (node (ref "J1") (pin "38") (pinfunction "38_38") (pintype "bidirectional"))
    )
    (net (code "50") (name "LCD_CL") (class "Default")
      (node (ref "IC1") (pin "21") (pinfunction "IOL_10B_21") (pintype "bidirectional"))
      (node (ref "J1") (pin "5") (pinfunction "5_5") (pintype "bidirectional"))
    )
    (net (code "51") (name "LCD_D0") (class "Default")
      (node (ref "IC1") (pin "27") (pinfunction "IOB_27_27") (pintype "bidirectional"))
      (node (ref "J1") (pin "12") (pinfunction "12_12") (pintype "bidirectional"))
    )
    (net (code "52") (name "LCD_D1") (class "Default")
      (node (ref "IC1") (pin "28") (pinfunction "IOB_28_28") (pintype "bidirectional"))
      (node (ref "J1") (pin "13") (pinfunction "13_13") (pintype "bidirectional"))
    )
    (net (code "53") (name "LCD_D2") (class "Default")
      (node (ref "IC1") (pin "29") (pinfunction "IOB_29_29") (pintype "bidirectional"))
      (node (ref "J1") (pin "14") (pinfunction "14_14") (pintype "bidirectional"))
    )
    (net (code "54") (name "LCD_D3") (class "Default")
      (node (ref "IC1") (pin "30") (pinfunction "IOB_30_30") (pintype "bidirectional"))
      (node (ref "J1") (pin "15") (pinfunction "15_15") (pintype "bidirectional"))
    )
    (net (code "55") (name "LCD_D4") (class "Default")
      (node (ref "IC1") (pin "33") (pinfunction "IOB_35_GBIN5_33") (pintype "bidirectional"))
      (node (ref "J1") (pin "16") (pinfunction "16_16") (pintype "bidirectional"))
    )
    (net (code "56") (name "LCD_D5") (class "Default")
      (node (ref "IC1") (pin "34") (pinfunction "IOB_36_GBIN4_34") (pintype "bidirectional"))
      (node (ref "J1") (pin "17") (pinfunction "17_17") (pintype "bidirectional"))
    )
    (net (code "57") (name "LCD_D6") (class "Default")
      (node (ref "IC1") (pin "36") (pinfunction "IOB_34_36") (pintype "bidirectional"))
      (node (ref "J1") (pin "18") (pinfunction "18_18") (pintype "bidirectional"))
    )
    (net (code "58") (name "LCD_D7") (class "Default")
      (node (ref "IC1") (pin "37") (pinfunction "IOB_37_37") (pintype "bidirectional"))
      (node (ref "J1") (pin "19") (pinfunction "19_19") (pintype "bidirectional"))
    )
    (net (code "59") (name "LCD_GMODE") (class "Default")
      (node (ref "IC1") (pin "40") (pinfunction "IOB_41_40") (pintype "bidirectional"))
      (node (ref "J1") (pin "27") (pinfunction "27_27") (pintype "bidirectional"))
      (node (ref "J1") (pin "28") (pinfunction "28_28") (pintype "bidirectional"))
    )
    (net (code "60") (name "LCD_GVDD") (class "Default")
      (node (ref "C25") (pin "1") (pinfunction "1_1") (pintype "passive"))
      (node (ref "D11") (pin "C") (pinfunction "C_C") (pintype "bidirectional"))
      (node (ref "J1") (pin "23") (pinfunction "23_23") (pintype "bidirectional"))
      (node (ref "R13") (pin "1") (pinfunction "1_1") (pintype "passive"))
      (node (ref "R15") (pin "2") (pinfunction "2_2") (pintype "passive"))
    )
    (net (code "61") (name "LCD_GVEE") (class "Default")
      (node (ref "C28") (pin "1") (pinfunction "1_1") (pintype "passive"))
      (node (ref "D13") (pin "A") (pinfunction "A_A") (pintype "bidirectional"))
      (node (ref "J1") (pin "24") (pinfunction "24_24") (pintype "bidirectional"))
      (node (ref "R11") (pin "2") (pinfunction "2_2") (pintype "passive"))
      (node (ref "R20") (pin "2") (pinfunction "2_2") (pintype "passive"))
    )
    (net (code "62") (name "LCD_LE") (class "Default")
      (node (ref "IC1") (pin "24") (pinfunction "IOL_12A_24") (pintype "bidirectional"))
      (node (ref "J1") (pin "6") (pinfunction "6_6") (pintype "bidirectional"))
    )
    (net (code "63") (name "LCD_OE") (class "Default")
      (node (ref "IC1") (pin "25") (pinfunction "IOL_12B_25") (pintype "bidirectional"))
      (node (ref "J1") (pin "7") (pinfunction "7_7") (pintype "bidirectional"))
    )
    (net (code "64") (name "LCD_SPH") (class "Default")
      (node (ref "IC1") (pin "26") (pinfunction "IOB_26_26") (pintype "bidirectional"))
      (node (ref "J1") (pin "11") (pinfunction "11_11") (pintype "bidirectional"))
    )
    (net (code "65") (name "LCD_SPV") (class "Default")
      (node (ref "IC1") (pin "41") (pinfunction "IOB_42_CBSEL0_41") (pintype "bidirectional"))
      (node (ref "J1") (pin "32") (pinfunction "32_32") (pintype "bidirectional"))
      (node (ref "J1") (pin "37") (pinfunction "37_37") (pintype "bidirectional"))
    )
    (net (code "66") (name "LCD_VCOM") (class "Default")
      (node (ref "C47") (pin "1") (pinfunction "1_1") (pintype "passive"))
      (node (ref "IC4") (pin "P15") (pinfunction "VCOM_P15") (pintype "bidirectional"))
      (node (ref "J1") (pin "22") (pinfunction "22_22") (pintype "bidirectional"))
      (node (ref "R17") (pin "2") (pinfunction "2_2") (pintype "passive"))
    )
    (net (code "67") (name "LCD_VNEG") (class "Default")
      (node (ref "C43") (pin "1") (pinfunction "1_1") (pintype "passive"))
      (node (ref "IC4") (pin "P$3") (pinfunction "VNEG_P$3") (pintype "bidirectional"))
      (node (ref "J1") (pin "1") (pinfunction "1_1") (pintype "bidirectional"))
      (node (ref "R16") (pin "2") (pinfunction "2_2") (pintype "passive"))
    )
    (net (code "68") (name "LCD_VPOS") (class "Default")
      (node (ref "C29") (pin "1") (pinfunction "1_1") (pintype "passive"))
      (node (ref "C48") (pin "2") (pinfunction "2_2") (pintype "passive"))
      (node (ref "IC4") (pin "P44") (pinfunction "VPOS_P44") (pintype "bidirectional"))
      (node (ref "J1") (pin "2") (pinfunction "2_2") (pintype "bidirectional"))
      (node (ref "R18") (pin "2") (pinfunction "2_2") (pintype "passive"))
    )
    (net (code "69") (name "N$39") (class "Default")
      (node (ref "J1") (pin "20") (pinfunction "20_20") (pintype "bidirectional"))
    )
    (net (code "70") (name "N$40") (class "Default")
      (node (ref "J1") (pin "21") (pinfunction "21_21") (pintype "bidirectional"))
    )
    (net (code "71") (name "Net-(C45-Pad2)") (class "Default")
      (node (ref "C45") (pin "2") (pinfunction "2_2") (pintype "passive"))
      (node (ref "D12") (pin "A") (pinfunction "A_A") (pintype "bidirectional"))
      (node (ref "D13") (pin "C") (pinfunction "C_C") (pintype "bidirectional"))
    )
    (net (code "72") (name "Net-(C46-Pad1)") (class "Default")
      (node (ref "C46") (pin "1") (pinfunction "1_1") (pintype "passive"))
      (node (ref "D10") (pin "C") (pinfunction "C_C") (pintype "bidirectional"))
      (node (ref "D11") (pin "A") (pinfunction "A_A") (pintype "bidirectional"))
    )
    (net (code "73") (name "Net-(IC3-CE#)") (class "Default")
      (node (ref "IC3") (pin "1") (pinfunction "CE#_1") (pintype "bidirectional"))
      (node (ref "R2") (pin "2") (pinfunction "2_2") (pintype "passive"))
      (node (ref "R3") (pin "1") (pinfunction "1_1") (pintype "passive"))
    )
    (net (code "74") (name "Net-(IC3-HOLD#)") (class "Default")
      (node (ref "IC3") (pin "3") (pinfunction "WP#_3") (pintype "bidirectional"))
      (node (ref "IC3") (pin "7") (pinfunction "HOLD#_7") (pintype "bidirectional"))
      (node (ref "R1") (pin "1") (pinfunction "1_1") (pintype "passive"))
    )
    (net (code "75") (name "Net-(IC4-INT_LDO)") (class "Default")
      (node (ref "C39") (pin "1") (pinfunction "1_1") (pintype "passive"))
      (node (ref "IC4") (pin "P$7") (pinfunction "INT_LDO_P$7") (pintype "bidirectional"))
    )
    (net (code "76") (name "Net-(IC4-TS)") (class "Default")
      (node (ref "IC4") (pin "P47") (pinfunction "TS_P47") (pintype "bidirectional"))
      (node (ref "NTC1") (pin "2") (pinfunction "2_2") (pintype "passive"))
      (node (ref "R19") (pin "2") (pinfunction "2_2") (pintype "passive"))
    )
    (net (code "77") (name "Net-(IC4-VB_SW)") (class "Default")
      (node (ref "D8") (pin "A") (pinfunction "A_A") (pintype "bidirectional"))
      (node (ref "IC4") (pin "P40") (pinfunction "VB_SW_P40") (pintype "bidirectional"))
      (node (ref "L3") (pin "P$2") (pinfunction "P$2_P$2") (pintype "bidirectional"))
    )
    (net (code "78") (name "Net-(IC4-VCOM_DIS)") (class "Default")
      (node (ref "IC4") (pin "P14") (pinfunction "VCOM_DIS_P14") (pintype "bidirectional"))
      (node (ref "R17") (pin "1") (pinfunction "1_1") (pintype "passive"))
    )
    (net (code "79") (name "Net-(IC4-VDDH_D)") (class "Default")
      (node (ref "C49") (pin "2") (pinfunction "2_2") (pintype "passive"))
      (node (ref "D10") (pin "A") (pinfunction "A_A") (pintype "bidirectional"))
      (node (ref "IC4") (pin "P34") (pinfunction "VDDH_D_P34") (pintype "bidirectional"))
    )
    (net (code "80") (name "Net-(IC4-VDDH_DIS)") (class "Default")
      (node (ref "IC4") (pin "P35") (pinfunction "VDDH_DIS_P35") (pintype "bidirectional"))
      (node (ref "R15") (pin "1") (pinfunction "1_1") (pintype "passive"))
    )
    (net (code "81") (name "Net-(IC4-VDDH_DRV)") (class "Default")
      (node (ref "C46") (pin "2") (pinfunction "2_2") (pintype "passive"))
      (node (ref "IC4") (pin "P36") (pinfunction "VDDH_DRV_P36") (pintype "bidirectional"))
    )
    (net (code "82") (name "Net-(IC4-VDDH_FB)") (class "Default")
      (node (ref "IC4") (pin "P33") (pinfunction "VDDH_FB_P33") (pintype "bidirectional"))
      (node (ref "R13") (pin "2") (pinfunction "2_2") (pintype "passive"))
      (node (ref "R14") (pin "1") (pinfunction "1_1") (pintype "passive"))
    )
    (net (code "83") (name "Net-(IC4-VEE_D)") (class "Default")
      (node (ref "C50") (pin "1") (pinfunction "1_1") (pintype "passive"))
      (node (ref "D12") (pin "C") (pinfunction "C_C") (pintype "bidirectional"))
      (node (ref "IC4") (pin "P30") (pinfunction "VEE_D_P30") (pintype "bidirectional"))
    )
    (net (code "84") (name "Net-(IC4-VEE_DIS)") (class "Default")
      (node (ref "IC4") (pin "P29") (pinfunction "VEE_DIS_P29") (pintype "bidirectional"))
      (node (ref "R20") (pin "1") (pinfunction "1_1") (pintype "passive"))
    )
    (net (code "85") (name "Net-(IC4-VEE_DRV)") (class "Default")
      (node (ref "C45") (pin "1") (pinfunction "1_1") (pintype "passive"))
      (node (ref "IC4") (pin "P28") (pinfunction "VEE_DRV_P28") (pintype "bidirectional"))
    )
    (net (code "86") (name "Net-(IC4-VEE_FB)") (class "Default")
      (node (ref "IC4") (pin "P31") (pinfunction "VEE_FB_P31") (pintype "bidirectional"))
      (node (ref "R11") (pin "1") (pinfunction "1_1") (pintype "passive"))
      (node (ref "R12") (pin "2") (pinfunction "2_2") (pintype "passive"))
    )
    (net (code "87") (name "Net-(IC4-VNEG_DIS)") (class "Default")
      (node (ref "IC4") (pin "P$9") (pinfunction "VNEG_DIS_P$9") (pintype "bidirectional"))
      (node (ref "R16") (pin "1") (pinfunction "1_1") (pintype "passive"))
    )
    (net (code "88") (name "Net-(IC4-VN_SW)") (class "Default")
      (node (ref "D9") (pin "C") (pinfunction "C_C") (pintype "bidirectional"))
      (node (ref "IC4") (pin "P25") (pinfunction "VN_SW_P25") (pintype "bidirectional"))
      (node (ref "L4") (pin "P$1") (pinfunction "P$1_P$1") (pintype "bidirectional"))
    )
    (net (code "89") (name "Net-(IC4-VPOS_DIS)") (class "Default")
      (node (ref "IC4") (pin "P19") (pinfunction "VPOS_DIS_P19") (pintype "bidirectional"))
      (node (ref "R18") (pin "1") (pinfunction "1_1") (pintype "passive"))
    )
    (net (code "90") (name "Net-(IC4-VREF)") (class "Default")
      (node (ref "C44") (pin "1") (pinfunction "1_1") (pintype "passive"))
      (node (ref "IC4") (pin "P$1") (pinfunction "VREF_P$1") (pintype "bidirectional"))
    )
    (net (code "91") (name "Net-(IC5-FB)") (class "Default")
      (node (ref "C17") (pin "1") (pinfunction "1_1") (pintype "passive"))
      (node (ref "IC5") (pin "5") (pinfunction "FB_5") (pintype "bidirectional"))
      (node (ref "R8") (pin "2") (pinfunction "2_2") (pintype "passive"))
      (node (ref "R9") (pin "2") (pinfunction "2_2") (pintype "passive"))
    )
    (net (code "92") (name "Net-(IC5-SW)") (class "Default")
      (node (ref "IC5") (pin "3") (pinfunction "SW_3") (pintype "bidirectional"))
      (node (ref "L1") (pin "P$1") (pinfunction "P$1_P$1") (pintype "bidirectional"))
    )
    (net (code "93") (name "Net-(IC6-FB)") (class "Default")
      (node (ref "C23") (pin "1") (pinfunction "1_1") (pintype "passive"))
      (node (ref "IC6") (pin "5") (pinfunction "FB_5") (pintype "bidirectional"))
      (node (ref "R10") (pin "2") (pinfunction "2_2") (pintype "passive"))
      (node (ref "R21") (pin "2") (pinfunction "2_2") (pintype "passive"))
    )
    (net (code "94") (name "Net-(IC6-SW)") (class "Default")
      (node (ref "IC6") (pin "3") (pinfunction "SW_3") (pintype "bidirectional"))
      (node (ref "L2") (pin "P$1") (pinfunction "P$1_P$1") (pintype "bidirectional"))
    )
    (net (code "95") (name "Net-(LED1-PadC)") (class "Default")
      (node (ref "LED1") (pin "C") (pinfunction "C_C") (pintype "passive"))
      (node (ref "R7") (pin "2") (pinfunction "2_2") (pintype "passive"))
    )
    (net (code "96") (name "Net-(LED2-PadA)") (class "Default")
      (node (ref "LED2") (pin "A") (pinfunction "A_A") (pintype "passive"))
      (node (ref "R22") (pin "2") (pinfunction "2_2") (pintype "passive"))
    )
    (net (code "97") (name "PG_PIN") (class "Default")
      (node (ref "IC4") (pin "P23") (pinfunction "PWR_GOOD_P23") (pintype "bidirectional"))
      (node (ref "LED2") (pin "C") (pinfunction "C_C") (pintype "passive"))
    )
    (net (code "98") (name "SCL_PIN") (class "Default")
      (node (ref "IC4") (pin "P17") (pinfunction "SCL_P17") (pintype "bidirectional"))
      (node (ref "J2") (pin "11") (pinfunction "11_11") (pintype "passive"))
    )
    (net (code "99") (name "SDA_PIN") (class "Default")
      (node (ref "IC4") (pin "P18") (pinfunction "SDA_P18") (pintype "bidirectional"))
      (node (ref "J2") (pin "12") (pinfunction "12_12") (pintype "passive"))
    )
    (net (code "100") (name "SPI_CLK") (class "Default")
      (node (ref "IC1") (pin "1") (pinfunction "IOL_1A_1") (pintype "bidirectional"))
      (node (ref "J2") (pin "1") (pinfunction "1_1") (pintype "passive"))
    )
    (net (code "101") (name "SPI_CMD") (class "Default")
      (node (ref "IC1") (pin "8") (pinfunction "IOL_3B_8") (pintype "bidirectional"))
      (node (ref "J2") (pin "7") (pinfunction "7_7") (pintype "passive"))
    )
    (net (code "102") (name "SPI_CS") (class "Default")
      (node (ref "IC1") (pin "9") (pinfunction "IOL_5A_9") (pintype "bidirectional"))
      (node (ref "J2") (pin "6") (pinfunction "6_6") (pintype "passive"))
    )
    (net (code "103") (name "SPI_DATA0") (class "Default")
      (node (ref "IC1") (pin "2") (pinfunction "IOL_1B_2") (pintype "bidirectional"))
      (node (ref "J2") (pin "2") (pinfunction "2_2") (pintype "passive"))
    )
    (net (code "104") (name "SPI_DATA1") (class "Default")
      (node (ref "IC1") (pin "3") (pinfunction "IOL_2A_3") (pintype "bidirectional"))
      (node (ref "J2") (pin "3") (pinfunction "3_3") (pintype "passive"))
    )
    (net (code "105") (name "SPI_DATA2") (class "Default")
      (node (ref "IC1") (pin "4") (pinfunction "IOL_2B_4") (pintype "bidirectional"))
      (node (ref "J2") (pin "4") (pinfunction "4_4") (pintype "passive"))
    )
    (net (code "106") (name "SPI_DATA3") (class "Default")
      (node (ref "IC1") (pin "7") (pinfunction "IOL_3A_7") (pintype "bidirectional"))
      (node (ref "J2") (pin "5") (pinfunction "5_5") (pintype "passive"))
    )
    (net (code "107") (name "VB") (class "Default")
      (node (ref "C35") (pin "1") (pinfunction "1_1") (pintype "passive"))
      (node (ref "C36") (pin "1") (pinfunction "1_1") (pintype "passive"))
      (node (ref "D8") (pin "C") (pinfunction "C_C") (pintype "bidirectional"))
      (node (ref "IC4") (pin "P37") (pinfunction "VDDH_IN_P37") (pintype "bidirectional"))
      (node (ref "IC4") (pin "P42") (pinfunction "VB_P42") (pintype "bidirectional"))
      (node (ref "IC4") (pin "P43") (pinfunction "VPOS_IN_P43") (pintype "bidirectional"))
    )
    (net (code "108") (name "VIN") (class "Default")
      (node (ref "C21") (pin "1") (pinfunction "1_1") (pintype "passive"))
      (node (ref "C24") (pin "1") (pinfunction "1_1") (pintype "passive"))
      (node (ref "IC5") (pin "1") (pinfunction "EN_1") (pintype "bidirectional"))
      (node (ref "IC5") (pin "4") (pinfunction "VIN_4") (pintype "bidirectional"))
      (node (ref "IC6") (pin "1") (pinfunction "EN_1") (pintype "bidirectional"))
      (node (ref "IC6") (pin "4") (pinfunction "VIN_4") (pintype "bidirectional"))
      (node (ref "J2") (pin "14") (pinfunction "14_14") (pintype "passive"))
    )
    (net (code "109") (name "VN") (class "Default")
      (node (ref "C37") (pin "1") (pinfunction "1_1") (pintype "passive"))
      (node (ref "C41") (pin "1") (pinfunction "1_1") (pintype "passive"))
      (node (ref "C42") (pin "1") (pinfunction "1_1") (pintype "passive"))
      (node (ref "D9") (pin "A") (pinfunction "A_A") (pintype "bidirectional"))
      (node (ref "IC4") (pin "GN0") (pinfunction "POWER_PAD_GN0") (pintype "bidirectional"))
      (node (ref "IC4") (pin "GN1") (pinfunction "POWER_PAD_GN1") (pintype "bidirectional"))
      (node (ref "IC4") (pin "GN10") (pinfunction "POWER_PAD_GN10") (pintype "bidirectional"))
      (node (ref "IC4") (pin "GN11") (pinfunction "POWER_PAD_GN11") (pintype "bidirectional"))
      (node (ref "IC4") (pin "GN12") (pinfunction "POWER_PAD_GN12") (pintype "bidirectional"))
      (node (ref "IC4") (pin "GN13") (pinfunction "POWER_PAD_GN13") (pintype "bidirectional"))
      (node (ref "IC4") (pin "GN14") (pinfunction "POWER_PAD_GN14") (pintype "bidirectional"))
      (node (ref "IC4") (pin "GN15") (pinfunction "POWER_PAD_GN15") (pintype "bidirectional"))
      (node (ref "IC4") (pin "GN16") (pinfunction "POWER_PAD_GN16") (pintype "bidirectional"))
      (node (ref "IC4") (pin "GN2") (pinfunction "POWER_PAD_GN2") (pintype "bidirectional"))
      (node (ref "IC4") (pin "GN3") (pinfunction "POWER_PAD_GN3") (pintype "bidirectional"))
      (node (ref "IC4") (pin "GN4") (pinfunction "POWER_PAD_GN4") (pintype "bidirectional"))
      (node (ref "IC4") (pin "GN5") (pinfunction "POWER_PAD_GN5") (pintype "bidirectional"))
      (node (ref "IC4") (pin "GN6") (pinfunction "POWER_PAD_GN6") (pintype "bidirectional"))
      (node (ref "IC4") (pin "GN7") (pinfunction "POWER_PAD_GN7") (pintype "bidirectional"))
      (node (ref "IC4") (pin "GN8") (pinfunction "POWER_PAD_GN8") (pintype "bidirectional"))
      (node (ref "IC4") (pin "GN9") (pinfunction "POWER_PAD_GN9") (pintype "bidirectional"))
      (node (ref "IC4") (pin "P$4") (pinfunction "VNEG_IN_P$4") (pintype "bidirectional"))
      (node (ref "IC4") (pin "P16") (pinfunction "VCOM_PWR_P16") (pintype "bidirectional"))
      (node (ref "IC4") (pin "P22") (pinfunction "PBKG_P22") (pintype "bidirectional"))
      (node (ref "IC4") (pin "P26") (pinfunction "VN_P26") (pintype "bidirectional"))
      (node (ref "IC4") (pin "P27") (pinfunction "VEE_IN_P27") (pintype "bidirectional"))
    )
    (net (code "110") (name "WAKE_PIN") (class "Default")
      (node (ref "IC4") (pin "P$5") (pinfunction "WAKEUP_P$5") (pintype "bidirectional"))
      (node (ref "J2") (pin "9") (pinfunction "9_9") (pintype "passive"))
    )
    (net (code "111") (name "unconnected-(IC1-IOL_5B-Pad10)") (class "Default")
      (node (ref "IC1") (pin "10") (pinfunction "IOL_5B_10") (pintype "bidirectional"))
    )
    (net (code "112") (name "unconnected-(IC1-IOL_6A-Pad12)") (class "Default")
      (node (ref "IC1") (pin "12") (pinfunction "IOL_6A_12") (pintype "bidirectional"))
    )
    (net (code "113") (name "unconnected-(IC1-IOL_6B_GBIN7-Pad13)") (class "Default")
      (node (ref "IC1") (pin "13") (pinfunction "IOL_6B_GBIN7_13") (pintype "bidirectional"))
    )
    (net (code "114") (name "unconnected-(IC1-IOL_7B-Pad16)") (class "Default")
      (node (ref "IC1") (pin "16") (pinfunction "IOL_7B_16") (pintype "bidirectional"))
    )
    (net (code "115") (name "unconnected-(IC1-IOL_8A-Pad18)") (class "Default")
      (node (ref "IC1") (pin "18") (pinfunction "IOL_8A_18") (pintype "bidirectional"))
    )
    (net (code "116") (name "unconnected-(IC1-IOL_8B-Pad19)") (class "Default")
      (node (ref "IC1") (pin "19") (pinfunction "IOL_8B_19") (pintype "bidirectional"))
    )
    (net (code "117") (name "unconnected-(IC1-IOL_10A-Pad20)") (class "Default")
      (node (ref "IC1") (pin "20") (pinfunction "IOL_10A_20") (pintype "bidirectional"))
    )
    (net (code "118") (name "unconnected-(IC1-VPP_FAST-Pad76)") (class "Default")
      (node (ref "IC1") (pin "76") (pinfunction "VPP_FAST_76") (pintype "bidirectional"))
    )
    (net (code "119") (name "unconnected-(IC4-V3P3-PadP46)") (class "Default")
      (node (ref "IC4") (pin "P46") (pinfunction "V3P3_P46") (pintype "bidirectional"))
    )
    (net (code "120") (name "unconnected-(J1-Pad25)") (class "Default")
      (node (ref "J1") (pin "25") (pinfunction "25_25") (pintype "bidirectional"))
    )
    (net (code "121") (name "unconnected-(J1-Pad26)") (class "Default")
      (node (ref "J1") (pin "26") (pinfunction "26_26") (pintype "bidirectional"))
    )
    (net (code "122") (name "unconnected-(J1-Pad39)") (class "Default")
      (node (ref "J1") (pin "39") (pinfunction "39_39") (pintype "bidirectional"))
    )
    (net (code "123") (name "unconnected-(X1-Pad1)") (class "Default")
      (node (ref "X1") (pin "1") (pinfunction "1_1") (pintype "bidirectional"))
    )
    (net (code "124") (name "~{CE}") (class "Default")
      (node (ref "IC1") (pin "54") (pinfunction "IOR_55_54") (pintype "bidirectional"))
      (node (ref "IC2") (pin "6") (pinfunction "~{CE}_6") (pintype "bidirectional"))
      (node (ref "R4") (pin "2") (pinfunction "2_2") (pintype "passive"))
    )
    (net (code "125") (name "~{OE}") (class "Default")
      (node (ref "IC1") (pin "51") (pinfunction "IOR_52_51") (pintype "bidirectional"))
      (node (ref "IC2") (pin "41") (pinfunction "~{OE}_41") (pintype "bidirectional"))
    )
    (net (code "126") (name "~{WE}") (class "Default")
      (node (ref "IC1") (pin "74") (pinfunction "IOR_72_74") (pintype "bidirectional"))
      (node (ref "IC2") (pin "17") (pinfunction "~{WE}_17") (pintype "bidirectional"))
    )
  )
)
